# Charger.net
KiCad netlist of a schematic drawn in EAGLE
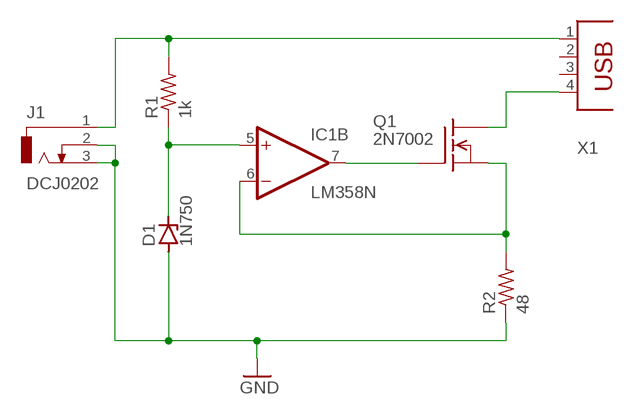
[diagram p0: schematic, sheet 1]

(export (version "E")
  (design (tool "Eeschema 10.0.6"))
  (components
    (comp (ref "D1")
      (value "1N750")
      (footprint "eagle-import:DO35Z10")
      (libsource (lib "eagle-import") (part "ZENER-DIODEDO35Z10"))
    )
    (comp (ref "IC1")
      (value "LM358N")
      (footprint "eagle-import:DIL08")
      (libsource (lib "eagle-import") (part "LM358N"))
    )
    (comp (ref "J1")
      (value "DCJ0202")
      (footprint "eagle-import:DCJ0202")
      (libsource (lib "eagle-import") (part "DCJ0202"))
    )
    (comp (ref "Q1")
      (value "2N7002")
      (footprint "eagle-import:TO-92")
      (libsource (lib "eagle-import") (part "TN0602N3"))
    )
    (comp (ref "R1")
      (value "1k")
      (footprint "eagle-import:0204_7")
      (libsource (lib "eagle-import") (part "R-US_0204/7"))
    )
    (comp (ref "R2")
      (value "48")
      (footprint "eagle-import:0204_7")
      (libsource (lib "eagle-import") (part "R-US_0204/7"))
    )
    (comp (ref "X1")
      (value "PN87520")
      (footprint "eagle-import:PN87520")
      (libsource (lib "eagle-import") (part "PN87520"))
    )
  )
  (nets
    (net (code "1") (name "GND") (class "Default")
      (node (ref "D1") (pin "A") (pinfunction "A_A") (pintype "passive"))
      (node (ref "J1") (pin "2") (pinfunction "2_2") (pintype "passive"))
      (node (ref "J1") (pin "3") (pinfunction "3_3") (pintype "passive"))
      (node (ref "R2") (pin "1") (pinfunction "1_1") (pintype "passive"))
    )
    (net (code "2") (name "Net-(IC1B-+IN)") (class "Default")
      (node (ref "D1") (pin "C") (pinfunction "C_C") (pintype "passive"))
      (node (ref "IC1") (pin "5") (pinfunction "+IN_5") (pintype "input"))
      (node (ref "R1") (pin "1") (pinfunction "1_1") (pintype "passive"))
    )
    (net (code "3") (name "Net-(IC1B--IN)") (class "Default")
      (node (ref "IC1") (pin "6") (pinfunction "-IN_6") (pintype "input"))
      (node (ref "Q1") (pin "1") (pinfunction "S_1") (pintype "passive"))
      (node (ref "R2") (pin "2") (pinfunction "2_2") (pintype "passive"))
    )
    (net (code "4") (name "Net-(IC1B-OUT)") (class "Default")
      (node (ref "IC1") (pin "7") (pinfunction "OUT_7") (pintype "output"))
      (node (ref "Q1") (pin "2") (pinfunction "G_2") (pintype "passive"))
    )
    (net (code "5") (name "Net-(J1-Pad1)") (class "Default")
      (node (ref "J1") (pin "1") (pinfunction "1_1") (pintype "passive"))
      (node (ref "R1") (pin "2") (pinfunction "2_2") (pintype "passive"))
      (node (ref "X1") (pin "1") (pinfunction "1_1") (pintype "passive"))
    )
    (net (code "6") (name "Net-(Q1-D)") (class "Default")
      (node (ref "Q1") (pin "3") (pinfunction "D_3") (pintype "passive"))
      (node (ref "X1") (pin "4") (pinfunction "4_4") (pintype "passive"))
    )
    (net (code "7") (name "unconnected-(X1-Pad2)") (class "Default")
      (node (ref "X1") (pin "2") (pinfunction "2_2") (pintype "passive"))
    )
    (net (code "8") (name "unconnected-(X1-Pad3)") (class "Default")
      (node (ref "X1") (pin "3") (pinfunction "3_3") (pintype "passive"))
    )
  )
)
